# design.net
KiCad netlist of a schematic drawn in Altium Designer
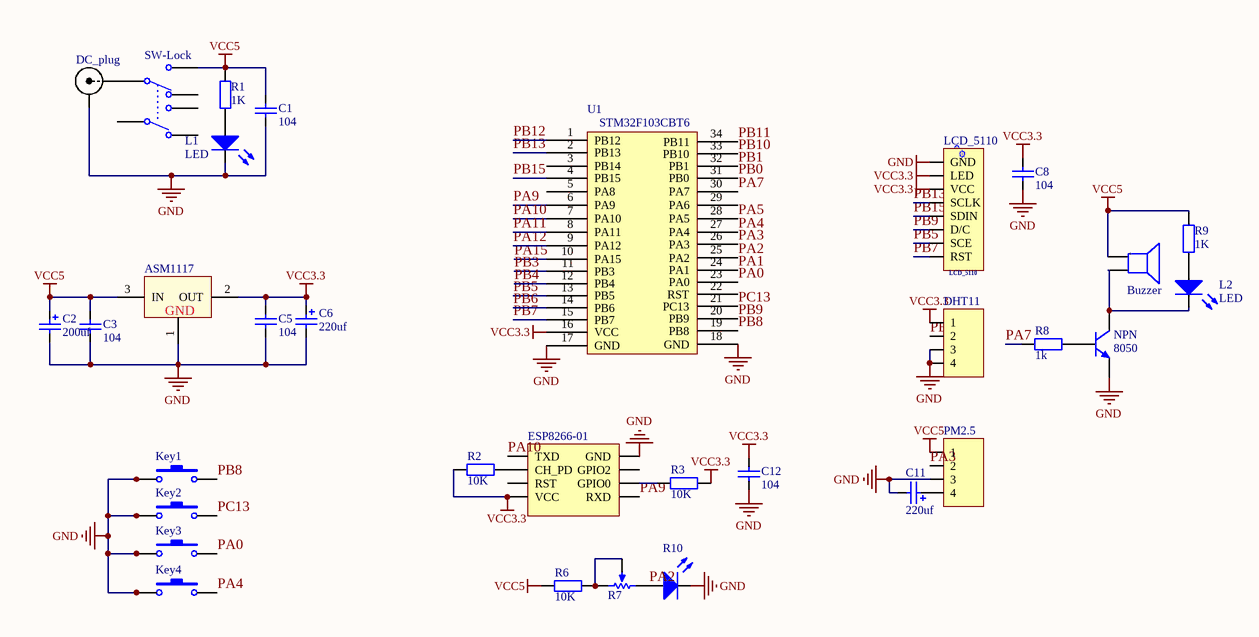
[diagram p0: 原理图 .SchDoc]

(export (version "E")
  (design (tool "Eeschema 10.0.6"))
  (components
    (comp (ref "ASM1117") (value "~") (footprint "ASM1117") (libsource (lib "componlib") (part "ASM1117")))
    (comp (ref "Buzzer") (value "~") (footprint "Buzzer") (libsource (lib "componlib") (part "Buzzer")))
    (comp (ref "C1")
      (value "104")
      (footprint "CAP_ceramic_1*0.8")
      (libsource (lib "componlib") (part "Cap_ceramic"))
    )
    (comp (ref "C2")
      (value "200uf")
      (footprint "CAP_elect_1*2")
      (libsource (lib "componlib") (part "Cap_elect_1"))
    )
    (comp (ref "C3")
      (value "104")
      (footprint "CAP_ceramic_1*0.8")
      (libsource (lib "componlib") (part "Cap_ceramic"))
    )
    (comp (ref "C5")
      (value "104")
      (footprint "CAP_ceramic_1*0.8")
      (libsource (lib "componlib") (part "Cap_ceramic"))
    )
    (comp (ref "C6")
      (value "220uf")
      (footprint "CAP_elect_1*2")
      (libsource (lib "componlib") (part "Cap_elect_1"))
    )
    (comp (ref "C8")
      (value "104")
      (footprint "CAP_ceramic_1*0.8")
      (libsource (lib "componlib") (part "Cap_ceramic"))
    )
    (comp (ref "C11")
      (value "220uf")
      (footprint "CAP_elect_2*2")
      (libsource (lib "Storeroom") (part "Cap_elect_1"))
    )
    (comp (ref "C12")
      (value "104")
      (footprint "CAP_ceramic_1*0.8")
      (libsource (lib "componlib") (part "Cap_ceramic"))
    )
    (comp (ref "DC_plug") (value "~") (footprint "DC_plug") (libsource (lib "componlib") (part "DC_plug")))
    (comp (ref "DHT11") (value "~") (footprint "PIN_4") (libsource (lib "Pluggable") (part "PIN_4")))
    (comp (ref "ESP8266-01")
      (value "~")
      (footprint "ESP8266-01")
      (libsource (lib "componlib") (part "ESP8266-01"))
    )
    (comp (ref "Key1") (value "~") (footprint "KEY_1") (libsource (lib "Storeroom") (part "Key")))
    (comp (ref "Key2") (value "~") (footprint "KEY_1") (libsource (lib "Storeroom") (part "Key")))
    (comp (ref "Key3") (value "~") (footprint "KEY_1") (libsource (lib "Storeroom") (part "Key")))
    (comp (ref "Key4") (value "~") (footprint "KEY_1") (libsource (lib "Storeroom") (part "Key")))
    (comp (ref "L1") (value "LED") (footprint "LED_R") (libsource (lib "componlib") (part "LED")))
    (comp (ref "L2") (value "LED") (footprint "LED_R") (libsource (lib "componlib") (part "LED")))
    (comp (ref "LCD_5110") (value "~") (footprint "LCD_5110") (libsource (lib "componlib") (part "LCD_5110")))
    (comp (ref "NPN") (value "8050") (footprint "NPN/PNP_DIP_1") (libsource (lib "componlib") (part "NPN")))
    (comp (ref "PM2.5") (value "~") (footprint "PIN_4") (libsource (lib "Pluggable") (part "PIN_4")))
    (comp (ref "R1") (value "1K") (footprint "RES_TOR_0.4") (libsource (lib "") (part "Res1_1")))
    (comp (ref "R2") (value "10K") (footprint "RES_TOR_0.4") (libsource (lib "componlib") (part "Res1")))
    (comp (ref "R3") (value "10K") (footprint "RES_TOR_0.4") (libsource (lib "componlib") (part "Res1")))
    (comp (ref "R6") (value "10K") (footprint "RES_TOR_0.4") (libsource (lib "componlib") (part "Res1")))
    (comp (ref "R7") (value "~") (footprint "RES_POT_1") (libsource (lib "componlib") (part "Res_pot")))
    (comp (ref "R8") (value "1k") (footprint "RES_TOR_0.4") (libsource (lib "componlib") (part "Res1")))
    (comp (ref "R9") (value "1K") (footprint "RES_TOR_0.4") (libsource (lib "") (part "Res1_1")))
    (comp (ref "R10") (value "~") (footprint "LED_R") (libsource (lib "componlib") (part "LED")))
    (comp (ref "SW-Lock") (value "~") (footprint "SW-LOCK") (libsource (lib "componlib") (part "SW-Lock")))
    (comp (ref "U1")
      (value "STM32F103CBT6最小系统")
      (footprint "STM32F103CBT6")
      (libsource (lib "componlib") (part "STM32F103CBT6最小系统"))
    )
  )
  (nets
    (net (code "1") (name "/PA0") (class "Default")
      (node (ref "Key3") (pin "2") (pinfunction "2_2") (pintype "passive"))
      (node (ref "Key3") (pin "4") (pinfunction "4_4") (pintype "passive"))
      (node (ref "U1") (pin "23") (pinfunction "PA0_23") (pintype "passive"))
    )
    (net (code "2") (name "/PA1") (class "Default")
      (node (ref "U1") (pin "24") (pinfunction "PA1_24") (pintype "passive"))
    )
    (net (code "3") (name "/PA2") (class "Default")
      (node (ref "R10") (pin "1") (pinfunction "A_1") (pintype "passive"))
      (node (ref "R7") (pin "3") (pinfunction "3_3") (pintype "passive"))
      (node (ref "U1") (pin "25") (pinfunction "PA2_25") (pintype "passive"))
    )
    (net (code "4") (name "/PA3") (class "Default")
      (node (ref "PM2.5") (pin "2") (pinfunction "2_2") (pintype "passive"))
      (node (ref "U1") (pin "26") (pinfunction "PA3_26") (pintype "passive"))
    )
    (net (code "5") (name "/PA4") (class "Default")
      (node (ref "Key4") (pin "2") (pinfunction "2_2") (pintype "passive"))
      (node (ref "Key4") (pin "4") (pinfunction "4_4") (pintype "passive"))
      (node (ref "U1") (pin "27") (pinfunction "PA4_27") (pintype "passive"))
    )
    (net (code "6") (name "/PA5") (class "Default")
      (node (ref "U1") (pin "28") (pinfunction "PA5_28") (pintype "passive"))
    )
    (net (code "7") (name "/PA7") (class "Default")
      (node (ref "R8") (pin "1") (pinfunction "1_1") (pintype "passive"))
      (node (ref "U1") (pin "30") (pinfunction "PA7_30") (pintype "passive"))
    )
    (net (code "8") (name "/PA9") (class "Default")
      (node (ref "ESP8266-01") (pin "5") (pinfunction "RXD_5") (pintype "passive"))
      (node (ref "U1") (pin "6") (pinfunction "PA9_6") (pintype "passive"))
    )
    (net (code "9") (name "/PA10") (class "Default")
      (node (ref "ESP8266-01") (pin "1") (pinfunction "TXD_1") (pintype "passive"))
      (node (ref "U1") (pin "7") (pinfunction "PA10_7") (pintype "passive"))
    )
    (net (code "10") (name "/PA11") (class "Default")
      (node (ref "U1") (pin "8") (pinfunction "PA11_8") (pintype "passive"))
    )
    (net (code "11") (name "/PA12") (class "Default")
      (node (ref "U1") (pin "9") (pinfunction "PA12_9") (pintype "passive"))
    )
    (net (code "12") (name "/PA15") (class "Default")
      (node (ref "U1") (pin "10") (pinfunction "PA15_10") (pintype "passive"))
    )
    (net (code "13") (name "/PB0") (class "Default")
      (node (ref "U1") (pin "31") (pinfunction "PB0_31") (pintype "passive"))
    )
    (net (code "14") (name "/PB1") (class "Default")
      (node (ref "U1") (pin "32") (pinfunction "PB1_32") (pintype "passive"))
    )
    (net (code "15") (name "/PB3") (class "Default")
      (node (ref "U1") (pin "11") (pinfunction "PB3_11") (pintype "passive"))
    )
    (net (code "16") (name "/PB4") (class "Default")
      (node (ref "U1") (pin "12") (pinfunction "PB4_12") (pintype "passive"))
    )
    (net (code "17") (name "/PB5") (class "Default")
      (node (ref "LCD_5110") (pin "7") (pinfunction "SCE_7") (pintype "passive"))
      (node (ref "U1") (pin "13") (pinfunction "PB5_13") (pintype "passive"))
    )
    (net (code "18") (name "/PB6") (class "Default")
      (node (ref "U1") (pin "14") (pinfunction "PB6_14") (pintype "passive"))
    )
    (net (code "19") (name "/PB7") (class "Default")
      (node (ref "LCD_5110") (pin "8") (pinfunction "RST_8") (pintype "passive"))
      (node (ref "U1") (pin "15") (pinfunction "PB7_15") (pintype "passive"))
    )
    (net (code "20") (name "/PB8") (class "Default")
      (node (ref "Key1") (pin "2") (pinfunction "2_2") (pintype "passive"))
      (node (ref "Key1") (pin "4") (pinfunction "4_4") (pintype "passive"))
      (node (ref "U1") (pin "19") (pinfunction "PB8_19") (pintype "passive"))
    )
    (net (code "21") (name "/PB9") (class "Default")
      (node (ref "LCD_5110") (pin "6") (pinfunction "D/C_6") (pintype "passive"))
      (node (ref "U1") (pin "20") (pinfunction "PB9_20") (pintype "passive"))
    )
    (net (code "22") (name "/PB10") (class "Default")
      (node (ref "U1") (pin "33") (pinfunction "PB10_33") (pintype "passive"))
    )
    (net (code "23") (name "/PB11") (class "Default")
      (node (ref "U1") (pin "34") (pinfunction "PB11_34") (pintype "passive"))
    )
    (net (code "24") (name "/PB12") (class "Default")
      (node (ref "DHT11") (pin "2") (pinfunction "2_2") (pintype "passive"))
      (node (ref "U1") (pin "1") (pinfunction "PB12_1") (pintype "passive"))
    )
    (net (code "25") (name "/PB13") (class "Default")
      (node (ref "LCD_5110") (pin "4") (pinfunction "SCLK_4") (pintype "passive"))
      (node (ref "U1") (pin "2") (pinfunction "PB13_2") (pintype "passive"))
    )
    (net (code "26") (name "/PB15") (class "Default")
      (node (ref "LCD_5110") (pin "5") (pinfunction "SDIN_5") (pintype "passive"))
      (node (ref "U1") (pin "4") (pinfunction "PB15_4") (pintype "passive"))
    )
    (net (code "27") (name "/PC13") (class "Default")
      (node (ref "Key2") (pin "2") (pinfunction "2_2") (pintype "passive"))
      (node (ref "Key2") (pin "4") (pinfunction "4_4") (pintype "passive"))
      (node (ref "U1") (pin "21") (pinfunction "PC13_21") (pintype "passive"))
    )
    (net (code "28") (name "GND") (class "Default")
      (node (ref "ASM1117") (pin "1") (pinfunction "GND_1") (pintype "passive"))
      (node (ref "C1") (pin "1") (pinfunction "1_1") (pintype "passive"))
      (node (ref "C11") (pin "2") (pinfunction "2_2") (pintype "passive"))
      (node (ref "C12") (pin "1") (pinfunction "1_1") (pintype "passive"))
      (node (ref "C2") (pin "2") (pinfunction "2_2") (pintype "passive"))
      (node (ref "C3") (pin "1") (pinfunction "1_1") (pintype "passive"))
      (node (ref "C5") (pin "2") (pinfunction "2_2") (pintype "passive"))
      (node (ref "C6") (pin "2") (pinfunction "2_2") (pintype "passive"))
      (node (ref "C8") (pin "1") (pinfunction "1_1") (pintype "passive"))
      (node (ref "DC_plug") (pin "2") (pinfunction "GND_2") (pintype "passive"))
      (node (ref "DHT11") (pin "3") (pinfunction "3_3") (pintype "passive"))
      (node (ref "DHT11") (pin "4") (pinfunction "4_4") (pintype "passive"))
      (node (ref "ESP8266-01") (pin "8") (pinfunction "GND_8") (pintype "passive"))
      (node (ref "Key1") (pin "1") (pinfunction "1_1") (pintype "passive"))
      (node (ref "Key1") (pin "3") (pinfunction "3_3") (pintype "passive"))
      (node (ref "Key2") (pin "1") (pinfunction "1_1") (pintype "passive"))
      (node (ref "Key2") (pin "3") (pinfunction "3_3") (pintype "passive"))
      (node (ref "Key3") (pin "1") (pinfunction "1_1") (pintype "passive"))
      (node (ref "Key3") (pin "3") (pinfunction "3_3") (pintype "passive"))
      (node (ref "Key4") (pin "1") (pinfunction "1_1") (pintype "passive"))
      (node (ref "Key4") (pin "3") (pinfunction "3_3") (pintype "passive"))
      (node (ref "L1") (pin "2") (pinfunction "K_2") (pintype "passive"))
      (node (ref "LCD_5110") (pin "1") (pinfunction "GND_1") (pintype "passive"))
      (node (ref "NPN") (pin "1") (pinfunction "E_1") (pintype "passive"))
      (node (ref "PM2.5") (pin "3") (pinfunction "3_3") (pintype "passive"))
      (node (ref "R10") (pin "2") (pinfunction "K_2") (pintype "passive"))
      (node (ref "U1") (pin "17") (pinfunction "GND_17") (pintype "passive"))
      (node (ref "U1") (pin "18") (pinfunction "GND_18") (pintype "passive"))
    )
    (net (code "29") (name "Net-(C11-Pad1)") (class "Default")
      (node (ref "C11") (pin "1") (pinfunction "1_1") (pintype "passive"))
      (node (ref "PM2.5") (pin "4") (pinfunction "4_4") (pintype "passive"))
    )
    (net (code "30") (name "Net-(DC_plug-VCC)") (class "Default")
      (node (ref "DC_plug") (pin "1") (pinfunction "VCC_1") (pintype "passive"))
      (node (ref "SW-Lock") (pin "6") (pinfunction "6_6") (pintype "passive"))
    )
    (net (code "31") (name "Net-(ESP8266-01-CH_PD)") (class "Default")
      (node (ref "ESP8266-01") (pin "2") (pinfunction "CH_PD_2") (pintype "passive"))
      (node (ref "R2") (pin "2") (pinfunction "2_2") (pintype "passive"))
    )
    (net (code "32") (name "Net-(ESP8266-01-GPIO0)") (class "Default")
      (node (ref "ESP8266-01") (pin "6") (pinfunction "GPIO0_6") (pintype "passive"))
      (node (ref "R3") (pin "1") (pinfunction "1_1") (pintype "passive"))
    )
    (net (code "33") (name "Net-(L1-A)") (class "Default")
      (node (ref "L1") (pin "1") (pinfunction "A_1") (pintype "passive"))
      (node (ref "R1") (pin "1") (pinfunction "1_1") (pintype "passive"))
    )
    (net (code "34") (name "Net-(L2-A)") (class "Default")
      (node (ref "L2") (pin "1") (pinfunction "A_1") (pintype "passive"))
      (node (ref "R9") (pin "1") (pinfunction "1_1") (pintype "passive"))
    )
    (net (code "35") (name "Net-(L2-K)") (class "Default")
      (node (ref "Buzzer") (pin "2") (pinfunction "2_2") (pintype "passive"))
      (node (ref "L2") (pin "2") (pinfunction "K_2") (pintype "passive"))
      (node (ref "NPN") (pin "3") (pinfunction "C_3") (pintype "passive"))
    )
    (net (code "36") (name "Net-(NPN-B)") (class "Default")
      (node (ref "NPN") (pin "2") (pinfunction "B_2") (pintype "passive"))
      (node (ref "R8") (pin "2") (pinfunction "2_2") (pintype "passive"))
    )
    (net (code "37") (name "Net-(R6-Pad2)") (class "Default")
      (node (ref "R6") (pin "2") (pinfunction "2_2") (pintype "passive"))
      (node (ref "R7") (pin "1") (pinfunction "1_1") (pintype "passive"))
      (node (ref "R7") (pin "2") (pinfunction "2_2") (pintype "passive"))
    )
    (net (code "38") (name "VCC3.3") (class "Default")
      (node (ref "ASM1117") (pin "2") (pinfunction "OUT_2") (pintype "passive"))
      (node (ref "C12") (pin "2") (pinfunction "2_2") (pintype "passive"))
      (node (ref "C5") (pin "1") (pinfunction "1_1") (pintype "passive"))
      (node (ref "C6") (pin "1") (pinfunction "1_1") (pintype "passive"))
      (node (ref "C8") (pin "2") (pinfunction "2_2") (pintype "passive"))
      (node (ref "DHT11") (pin "1") (pinfunction "1_1") (pintype "passive"))
      (node (ref "ESP8266-01") (pin "4") (pinfunction "VCC_4") (pintype "passive"))
      (node (ref "LCD_5110") (pin "2") (pinfunction "LED_2") (pintype "passive"))
      (node (ref "LCD_5110") (pin "3") (pinfunction "VCC_3") (pintype "passive"))
      (node (ref "R2") (pin "1") (pinfunction "1_1") (pintype "passive"))
      (node (ref "R3") (pin "2") (pinfunction "2_2") (pintype "passive"))
      (node (ref "U1") (pin "16") (pinfunction "VCC_16") (pintype "passive"))
    )
    (net (code "39") (name "VCC5") (class "Default")
      (node (ref "ASM1117") (pin "3") (pinfunction "IN_3") (pintype "passive"))
      (node (ref "Buzzer") (pin "1") (pinfunction "1_1") (pintype "passive"))
      (node (ref "C1") (pin "2") (pinfunction "2_2") (pintype "passive"))
      (node (ref "C2") (pin "1") (pinfunction "1_1") (pintype "passive"))
      (node (ref "C3") (pin "2") (pinfunction "2_2") (pintype "passive"))
      (node (ref "PM2.5") (pin "1") (pinfunction "1_1") (pintype "passive"))
      (node (ref "R1") (pin "2") (pinfunction "2_2") (pintype "passive"))
      (node (ref "R6") (pin "1") (pinfunction "1_1") (pintype "passive"))
      (node (ref "R9") (pin "2") (pinfunction "2_2") (pintype "passive"))
      (node (ref "SW-Lock") (pin "5") (pinfunction "5_5") (pintype "passive"))
    )
    (net (code "40") (name "unconnected-(ESP8266-01-GPIO2-Pad7)") (class "Default")
      (node (ref "ESP8266-01") (pin "7") (pinfunction "GPIO2_7") (pintype "passive"))
    )
    (net (code "41") (name "unconnected-(ESP8266-01-RST-Pad3)") (class "Default")
      (node (ref "ESP8266-01") (pin "3") (pinfunction "RST_3") (pintype "passive"))
    )
    (net (code "42") (name "unconnected-(SW-Lock-Pad1)") (class "Default")
      (node (ref "SW-Lock") (pin "1") (pinfunction "1_1") (pintype "passive"))
    )
    (net (code "43") (name "unconnected-(SW-Lock-Pad2)") (class "Default")
      (node (ref "SW-Lock") (pin "2") (pinfunction "2_2") (pintype "passive"))
    )
    (net (code "44") (name "unconnected-(SW-Lock-Pad3)") (class "Default")
      (node (ref "SW-Lock") (pin "3") (pinfunction "3_3") (pintype "passive"))
    )
    (net (code "45") (name "unconnected-(SW-Lock-Pad4)") (class "Default")
      (node (ref "SW-Lock") (pin "4") (pinfunction "4_4") (pintype "passive"))
    )
    (net (code "46") (name "unconnected-(U1-PA6-Pad29)") (class "Default")
      (node (ref "U1") (pin "29") (pinfunction "PA6_29") (pintype "passive"))
    )
    (net (code "47") (name "unconnected-(U1-PA8-Pad5)") (class "Default")
      (node (ref "U1") (pin "5") (pinfunction "PA8_5") (pintype "passive"))
    )
    (net (code "48") (name "unconnected-(U1-PB14-Pad3)") (class "Default")
      (node (ref "U1") (pin "3") (pinfunction "PB14_3") (pintype "passive"))
    )
    (net (code "49") (name "unconnected-(U1-RST-Pad22)") (class "Default")
      (node (ref "U1") (pin "22") (pinfunction "RST_22") (pintype "passive"))
    )
  )
)
